# 04-POWERV2_3.net
KiCad netlist of a schematic drawn in Altium Designer
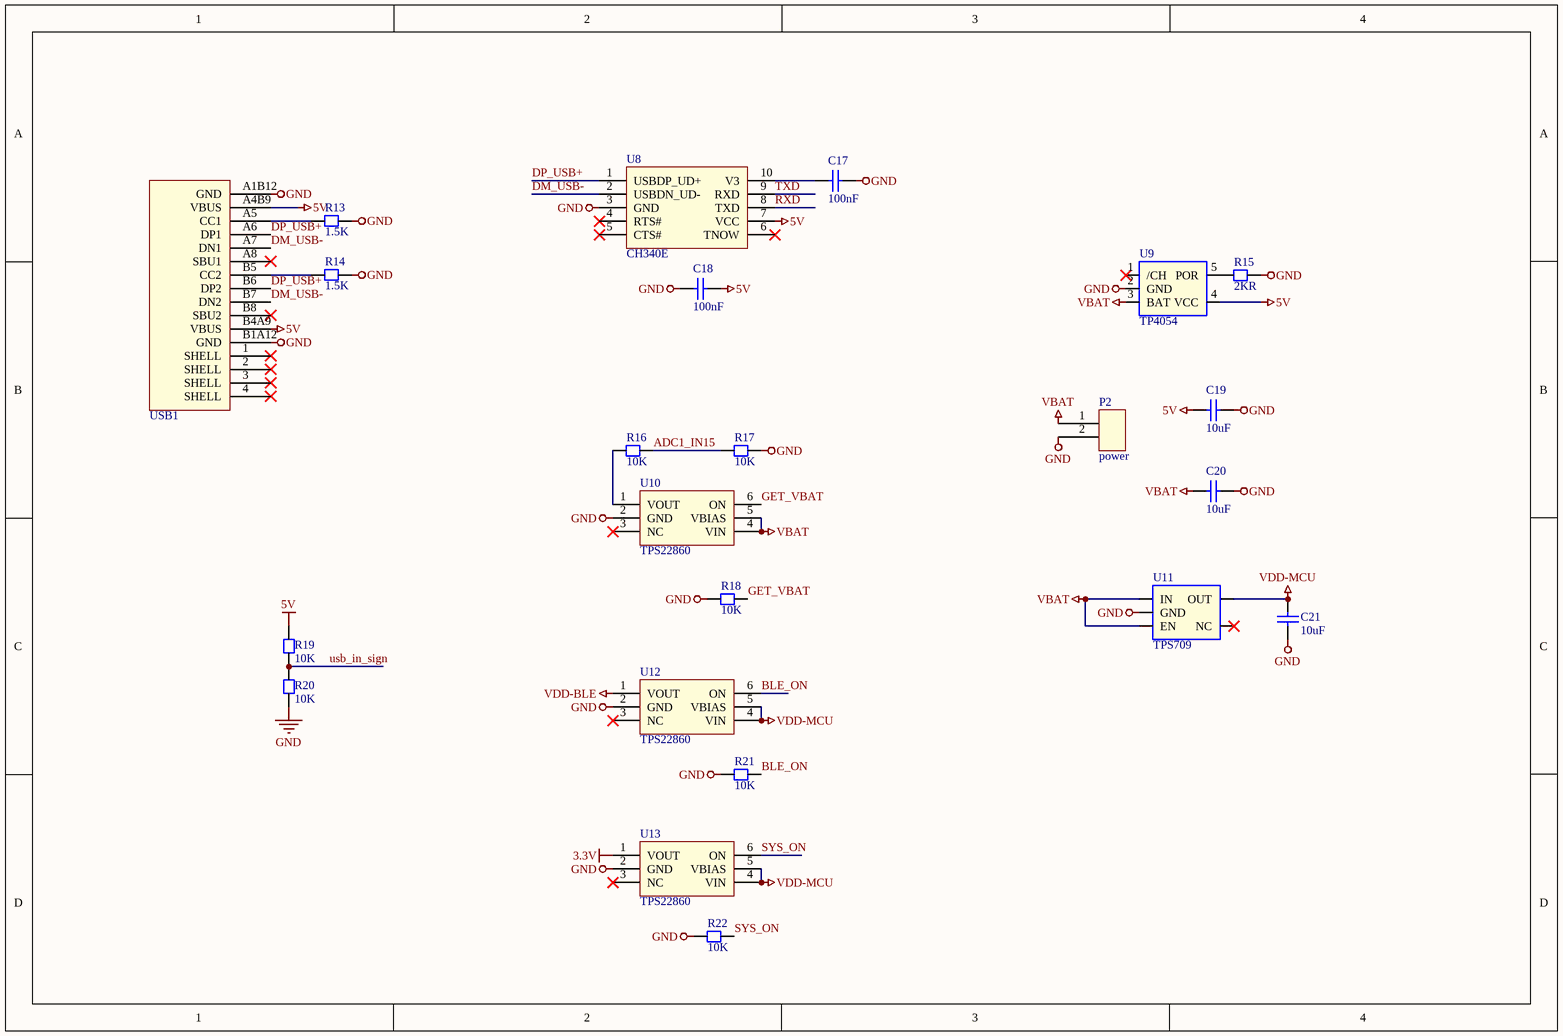
[diagram p0: 04-POWERV2.3.SchDoc]

(export (version "E")
  (design (tool "Eeschema 10.0.6"))
  (components
    (comp (ref "C17")
      (value "100nF")
      (footprint "CC1005-0402")
      (description "贴片电容")
      (libsource (lib "tianxiaohua_Schlib") (part "Chip capacitor"))
    )
    (comp (ref "C18")
      (value "100nF")
      (footprint "CC1005-0402")
      (description "贴片电容")
      (libsource (lib "tianxiaohua_Schlib") (part "Chip capacitor"))
    )
    (comp (ref "C19")
      (value "10uF")
      (footprint "CC1005-0402")
      (description "贴片电容")
      (libsource (lib "tianxiaohua_Schlib") (part "Chip capacitor"))
    )
    (comp (ref "C20")
      (value "10uF")
      (footprint "CC1005-0402")
      (description "贴片电容")
      (libsource (lib "tianxiaohua_Schlib") (part "Chip capacitor"))
    )
    (comp (ref "C21")
      (value "10uF")
      (footprint "CC1005-0402")
      (description "贴片电容")
      (libsource (lib "tianxiaohua_Schlib") (part "Chip capacitor"))
    )
    (comp (ref "P2")
      (value "power")
      (footprint "POWER-3.7V")
      (libsource (lib "tianxiaohua_Schlib") (part "power"))
    )
    (comp (ref "R13")
      (value "1.5K")
      (footprint "CR1005-0402")
      (description "贴片电阻")
      (libsource (lib "") (part "Chip resistor_2"))
    )
    (comp (ref "R14")
      (value "1.5K")
      (footprint "CR1005-0402")
      (description "贴片电阻")
      (libsource (lib "") (part "Chip resistor_2"))
    )
    (comp (ref "R15")
      (value "2KR")
      (footprint "CR1005-0402")
      (description "贴片电阻")
      (libsource (lib "") (part "Chip resistor_2"))
    )
    (comp (ref "R16")
      (value "10K")
      (footprint "CR1005-0402")
      (description "贴片电阻")
      (libsource (lib "") (part "Chip resistor_2"))
    )
    (comp (ref "R17")
      (value "10K")
      (footprint "CR1005-0402")
      (description "贴片电阻")
      (libsource (lib "") (part "Chip resistor_1"))
    )
    (comp (ref "R18")
      (value "10K")
      (footprint "CR1005-0402")
      (description "贴片电阻")
      (libsource (lib "") (part "Chip resistor_1"))
    )
    (comp (ref "R19")
      (value "10K")
      (footprint "CR1005-0402")
      (description "贴片电阻")
      (libsource (lib "tianxiaohua_Schlib") (part "Chip resistor"))
    )
    (comp (ref "R20")
      (value "10K")
      (footprint "CR1005-0402")
      (description "贴片电阻")
      (libsource (lib "tianxiaohua_Schlib") (part "Chip resistor"))
    )
    (comp (ref "R21")
      (value "10K")
      (footprint "CR1005-0402")
      (description "贴片电阻")
      (libsource (lib "") (part "Chip resistor_1"))
    )
    (comp (ref "R22")
      (value "10K")
      (footprint "CR1005-0402")
      (description "贴片电阻")
      (libsource (lib "") (part "Chip resistor_1"))
    )
    (comp (ref "U8")
      (value "CH340E")
      (footprint "MSOP-10")
      (description "usd转串口芯片 MSOP10封装")
      (libsource (lib "tianxiaohua_Schlib") (part "CH340E"))
    )
    (comp (ref "U9")
      (value "TP4054")
      (footprint "SOT23-5")
      (description "迷你充电IC SOT-23-5")
      (libsource (lib "tianxiaohua_Schlib") (part "TP4054"))
    )
    (comp (ref "U10")
      (value "TPS22860")
      (footprint "SOT23-6")
      (description "超低泄漏电流负载开关  超低泄漏电流负载开关 它可支持最大 200mA 的持续电\r流。 此开关可由一个打开/关闭输入 (ON) 控制")
      (libsource (lib "tianxiaohua_Schlib") (part "TPS22860"))
    )
    (comp (ref "U11")
      (value "TPS709")
      (footprint "SOT23-5")
      (description "3.3V降压IC SOT23-5封装 最大输出150ma电流")
      (libsource (lib "tianxiaohua_Schlib") (part "TPS709"))
    )
    (comp (ref "U12")
      (value "TPS22860")
      (footprint "SOT23-6")
      (description "超低泄漏电流负载开关  超低泄漏电流负载开关 它可支持最大 200mA 的持续电\r流。 此开关可由一个打开/关闭输入 (ON) 控制")
      (libsource (lib "tianxiaohua_Schlib") (part "TPS22860"))
    )
    (comp (ref "U13")
      (value "TPS22860")
      (footprint "SOT23-6")
      (description "超低泄漏电流负载开关  超低泄漏电流负载开关 它可支持最大 200mA 的持续电\r流。 此开关可由一个打开/关闭输入 (ON) 控制")
      (libsource (lib "tianxiaohua_Schlib") (part "TPS22860"))
    )
    (comp (ref "USB1")
      (value "Tpye-c 16P")
      (footprint "TYPE-C 16P")
      (description "16P 封装的TYPE -c接口 4固定插脚 双向")
      (libsource (lib "tianxiaohua_Schlib") (part "Tpye-c 16P"))
    )
  )
  (nets
    (net (code "1") (name "/ADC1_IN15") (class "Default")
      (node (ref "R16") (pin "1") (pinfunction "1_1") (pintype "passive"))
      (node (ref "R17") (pin "1") (pinfunction "1_1") (pintype "passive"))
    )
    (net (code "2") (name "/BLE_ON") (class "Default")
      (node (ref "R21") (pin "2") (pinfunction "2_2") (pintype "passive"))
      (node (ref "U12") (pin "6") (pinfunction "ON_6") (pintype "passive"))
    )
    (net (code "3") (name "/DM_USB-") (class "Default")
      (node (ref "U8") (pin "2") (pinfunction "USBDN_UD-_2") (pintype "passive"))
      (node (ref "USB1") (pin "A7") (pinfunction "DN1_A7") (pintype "power_in"))
      (node (ref "USB1") (pin "B7") (pinfunction "DN2_B7") (pintype "power_in"))
    )
    (net (code "4") (name "/DP_USB+") (class "Default")
      (node (ref "U8") (pin "1") (pinfunction "USBDP_UD+_1") (pintype "passive"))
      (node (ref "USB1") (pin "A6") (pinfunction "DP1_A6") (pintype "power_in"))
      (node (ref "USB1") (pin "B6") (pinfunction "DP2_B6") (pintype "power_in"))
    )
    (net (code "5") (name "/GET_VBAT") (class "Default")
      (node (ref "R18") (pin "2") (pinfunction "2_2") (pintype "passive"))
      (node (ref "U10") (pin "6") (pinfunction "ON_6") (pintype "passive"))
    )
    (net (code "6") (name "/RXD") (class "Default")
      (node (ref "U8") (pin "8") (pinfunction "TXD_8") (pintype "passive"))
    )
    (net (code "7") (name "/SYS_ON") (class "Default")
      (node (ref "R22") (pin "2") (pinfunction "2_2") (pintype "passive"))
      (node (ref "U13") (pin "6") (pinfunction "ON_6") (pintype "passive"))
    )
    (net (code "8") (name "/TXD") (class "Default")
      (node (ref "U8") (pin "9") (pinfunction "RXD_9") (pintype "passive"))
    )
    (net (code "9") (name "/usb_in_sign") (class "Default")
      (node (ref "R19") (pin "2") (pinfunction "2_2") (pintype "passive"))
      (node (ref "R20") (pin "1") (pinfunction "1_1") (pintype "passive"))
    )
    (net (code "10") (name "3.3V") (class "Default")
      (node (ref "U13") (pin "1") (pinfunction "VOUT_1") (pintype "passive"))
    )
    (net (code "11") (name "5V") (class "Default")
      (node (ref "C18") (pin "2") (pinfunction "2_2") (pintype "passive"))
      (node (ref "C19") (pin "2") (pinfunction "2_2") (pintype "passive"))
      (node (ref "R19") (pin "1") (pinfunction "1_1") (pintype "passive"))
      (node (ref "U8") (pin "7") (pinfunction "VCC_7") (pintype "passive"))
      (node (ref "U9") (pin "4") (pinfunction "VCC_4") (pintype "passive"))
      (node (ref "USB1") (pin "A4B9") (pinfunction "VBUS_A4B9") (pintype "power_in"))
      (node (ref "USB1") (pin "B4A9") (pinfunction "VBUS_B4A9") (pintype "power_in"))
    )
    (net (code "12") (name "GND") (class "Default")
      (node (ref "C17") (pin "2") (pinfunction "2_2") (pintype "passive"))
      (node (ref "C18") (pin "1") (pinfunction "1_1") (pintype "passive"))
      (node (ref "C19") (pin "1") (pinfunction "1_1") (pintype "passive"))
      (node (ref "C20") (pin "1") (pinfunction "1_1") (pintype "passive"))
      (node (ref "C21") (pin "2") (pinfunction "2_2") (pintype "passive"))
      (node (ref "P2") (pin "2") (pinfunction "2_2") (pintype "passive"))
      (node (ref "R13") (pin "1") (pinfunction "1_1") (pintype "passive"))
      (node (ref "R14") (pin "1") (pinfunction "1_1") (pintype "passive"))
      (node (ref "R15") (pin "1") (pinfunction "1_1") (pintype "passive"))
      (node (ref "R17") (pin "2") (pinfunction "2_2") (pintype "passive"))
      (node (ref "R18") (pin "1") (pinfunction "1_1") (pintype "passive"))
      (node (ref "R20") (pin "2") (pinfunction "2_2") (pintype "passive"))
      (node (ref "R21") (pin "1") (pinfunction "1_1") (pintype "passive"))
      (node (ref "R22") (pin "1") (pinfunction "1_1") (pintype "passive"))
      (node (ref "U10") (pin "2") (pinfunction "GND_2") (pintype "passive"))
      (node (ref "U11") (pin "2") (pinfunction "GND_2") (pintype "passive"))
      (node (ref "U12") (pin "2") (pinfunction "GND_2") (pintype "passive"))
      (node (ref "U13") (pin "2") (pinfunction "GND_2") (pintype "passive"))
      (node (ref "U8") (pin "3") (pinfunction "GND_3") (pintype "passive"))
      (node (ref "U9") (pin "2") (pinfunction "GND_2") (pintype "passive"))
      (node (ref "USB1") (pin "A1B12") (pinfunction "GND_A1B12") (pintype "power_in"))
      (node (ref "USB1") (pin "B1A12") (pinfunction "GND_B1A12") (pintype "power_in"))
    )
    (net (code "13") (name "Net-(U8-V3)") (class "Default")
      (node (ref "C17") (pin "1") (pinfunction "1_1") (pintype "passive"))
      (node (ref "U8") (pin "10") (pinfunction "V3_10") (pintype "passive"))
    )
    (net (code "14") (name "Net-(U9-POR)") (class "Default")
      (node (ref "R15") (pin "2") (pinfunction "2_2") (pintype "passive"))
      (node (ref "U9") (pin "5") (pinfunction "POR_5") (pintype "passive"))
    )
    (net (code "15") (name "Net-(U10-VOUT)") (class "Default")
      (node (ref "R16") (pin "2") (pinfunction "2_2") (pintype "passive"))
      (node (ref "U10") (pin "1") (pinfunction "VOUT_1") (pintype "passive"))
    )
    (net (code "16") (name "Net-(USB1-CC1)") (class "Default")
      (node (ref "R13") (pin "2") (pinfunction "2_2") (pintype "passive"))
      (node (ref "USB1") (pin "A5") (pinfunction "CC1_A5") (pintype "power_in"))
    )
    (net (code "17") (name "Net-(USB1-CC2)") (class "Default")
      (node (ref "R14") (pin "2") (pinfunction "2_2") (pintype "passive"))
      (node (ref "USB1") (pin "B5") (pinfunction "CC2_B5") (pintype "power_in"))
    )
    (net (code "18") (name "VBAT") (class "Default")
      (node (ref "C20") (pin "2") (pinfunction "2_2") (pintype "passive"))
      (node (ref "P2") (pin "1") (pinfunction "1_1") (pintype "passive"))
      (node (ref "U10") (pin "4") (pinfunction "VIN_4") (pintype "passive"))
      (node (ref "U10") (pin "5") (pinfunction "VBIAS_5") (pintype "passive"))
      (node (ref "U11") (pin "1") (pinfunction "IN_1") (pintype "passive"))
      (node (ref "U11") (pin "3") (pinfunction "EN_3") (pintype "passive"))
      (node (ref "U9") (pin "3") (pinfunction "BAT_3") (pintype "passive"))
    )
    (net (code "19") (name "VDD-BLE") (class "Default")
      (node (ref "U12") (pin "1") (pinfunction "VOUT_1") (pintype "passive"))
    )
    (net (code "20") (name "VDD-MCU") (class "Default")
      (node (ref "C21") (pin "1") (pinfunction "1_1") (pintype "passive"))
      (node (ref "U11") (pin "5") (pinfunction "OUT_5") (pintype "passive"))
      (node (ref "U12") (pin "4") (pinfunction "VIN_4") (pintype "passive"))
      (node (ref "U12") (pin "5") (pinfunction "VBIAS_5") (pintype "passive"))
      (node (ref "U13") (pin "4") (pinfunction "VIN_4") (pintype "passive"))
      (node (ref "U13") (pin "5") (pinfunction "VBIAS_5") (pintype "passive"))
    )
    (net (code "21") (name "unconnected-(U8-CTS#-Pad5)") (class "Default")
      (node (ref "U8") (pin "5") (pinfunction "CTS#_5") (pintype "passive+no_connect"))
    )
    (net (code "22") (name "unconnected-(U8-RTS#-Pad4)") (class "Default")
      (node (ref "U8") (pin "4") (pinfunction "RTS#_4") (pintype "passive+no_connect"))
    )
    (net (code "23") (name "unconnected-(U8-TNOW-Pad6)") (class "Default")
      (node (ref "U8") (pin "6") (pinfunction "TNOW_6") (pintype "passive+no_connect"))
    )
    (net (code "24") (name "unconnected-(U9-{slash}CH-Pad1)") (class "Default")
      (node (ref "U9") (pin "1") (pinfunction "/CH_1") (pintype "passive+no_connect"))
    )
    (net (code "25") (name "unconnected-(U10-NC-Pad3)") (class "Default")
      (node (ref "U10") (pin "3") (pinfunction "NC_3") (pintype "passive+no_connect"))
    )
    (net (code "26") (name "unconnected-(U11-NC-Pad4)") (class "Default")
      (node (ref "U11") (pin "4") (pinfunction "NC_4") (pintype "passive+no_connect"))
    )
    (net (code "27") (name "unconnected-(U12-NC-Pad3)") (class "Default")
      (node (ref "U12") (pin "3") (pinfunction "NC_3") (pintype "passive+no_connect"))
    )
    (net (code "28") (name "unconnected-(U13-NC-Pad3)") (class "Default")
      (node (ref "U13") (pin "3") (pinfunction "NC_3") (pintype "passive+no_connect"))
    )
    (net (code "29") (name "unconnected-(USB1-SBU1-PadA8)") (class "Default")
      (node (ref "USB1") (pin "A8") (pinfunction "SBU1_A8") (pintype "power_in+no_connect"))
    )
    (net (code "30") (name "unconnected-(USB1-SBU2-PadB8)") (class "Default")
      (node (ref "USB1") (pin "B8") (pinfunction "SBU2_B8") (pintype "power_in+no_connect"))
    )
    (net (code "31") (name "unconnected-(USB1-SHELL-Pad1)") (class "Default")
      (node (ref "USB1") (pin "1") (pinfunction "SHELL_1") (pintype "power_in+no_connect"))
    )
    (net (code "32") (name "unconnected-(USB1-SHELL-Pad2)") (class "Default")
      (node (ref "USB1") (pin "2") (pinfunction "SHELL_2") (pintype "power_in+no_connect"))
    )
    (net (code "33") (name "unconnected-(USB1-SHELL-Pad3)") (class "Default")
      (node (ref "USB1") (pin "3") (pinfunction "SHELL_3") (pintype "power_in+no_connect"))
    )
    (net (code "34") (name "unconnected-(USB1-SHELL-Pad4)") (class "Default")
      (node (ref "USB1") (pin "4") (pinfunction "SHELL_4") (pintype "power_in+no_connect"))
    )
  )
)
